# NewThermocouple.net
KiCad netlist of a schematic drawn in Altium Designer
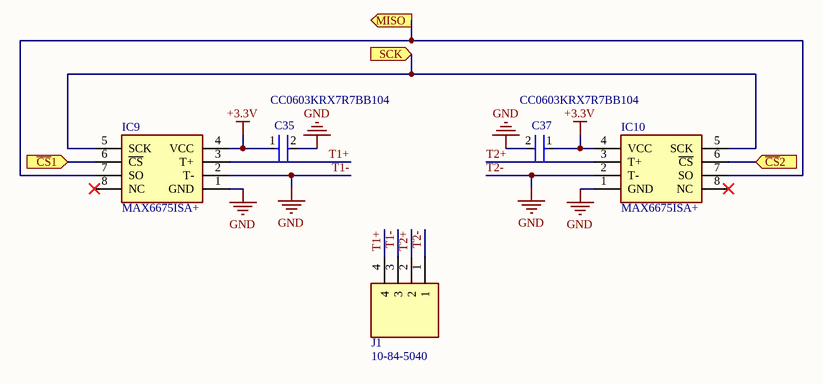
[diagram p0: NewThermocouple.SchDoc]

(export (version "E")
  (design (tool "Eeschema 10.0.6"))
  (components
    (comp (ref "C35")
      (value "CC0603KRX7R7BB104")
      (footprint "FP-CC0603-DA-MFG")
      (description "CAP CER 0.1UF 16V X7R 0603")
      (fields
        (field (name "OCTOPART") "https://octopart.com/cc0603krx7r7bb104-yageo-192941")
        (field (name "TOLERANCE") "0.1")
      )
      (libsource (lib "Altium Content Vault") (part "11868f565c42a9108669ba33697ecf6"))
    )
    (comp (ref "C37")
      (value "CC0603KRX7R7BB104")
      (footprint "FP-CC0603-DA-MFG")
      (description "CAP CER 0.1UF 16V X7R 0603")
      (fields
        (field (name "OCTOPART") "https://octopart.com/cc0603krx7r7bb104-yageo-192941")
        (field (name "TOLERANCE") "0.1")
      )
      (libsource (lib "Altium Content Vault") (part "11868f565c42a9108669ba33697ecf6"))
    )
    (comp (ref "IC9")
      (value "MAX6675ISA+")
      (footprint "SamacSys:SOIC127P600X175-8N")
      (description "Integrated Circuit")
      (fields (field (name "MOUSER2 PART NUMBER") "700-MAX6675ISA"))
      (libsource (lib "") (part "MAX6675ISA+_1"))
    )
    (comp (ref "IC10")
      (value "MAX6675ISA+")
      (footprint "SamacSys:SOIC127P600X175-8N")
      (description "Integrated Circuit")
      (fields (field (name "MOUSER2 PART NUMBER") "700-MAX6675ISA"))
      (libsource (lib "*") (part "MAX6675ISA+"))
    )
    (comp (ref "J1")
      (value "10-84-5040")
      (footprint "SamacSys:10845040")
      (description "Connector")
      (libsource (lib "*") (part "10-84-5040"))
    )
  )
  (nets
    (net (code "1") (name "+3.3V") (class "Default")
      (node (ref "C35") (pin "1") (pinfunction "1_1") (pintype "passive"))
      (node (ref "C37") (pin "1") (pinfunction "1_1") (pintype "passive"))
      (node (ref "IC10") (pin "4") (pinfunction "VCC_4") (pintype "passive"))
      (node (ref "IC9") (pin "4") (pinfunction "VCC_4") (pintype "passive"))
    )
    (net (code "2") (name "/MISO") (class "Default")
      (node (ref "IC10") (pin "7") (pinfunction "SO_7") (pintype "passive"))
      (node (ref "IC9") (pin "7") (pinfunction "SO_7") (pintype "passive"))
    )
    (net (code "3") (name "/SCK") (class "Default")
      (node (ref "IC10") (pin "5") (pinfunction "SCK_5") (pintype "passive"))
      (node (ref "IC9") (pin "5") (pinfunction "SCK_5") (pintype "passive"))
    )
    (net (code "4") (name "/T1+") (class "Default")
      (node (ref "IC9") (pin "3") (pinfunction "T+_3") (pintype "passive"))
      (node (ref "J1") (pin "4") (pinfunction "4_4") (pintype "passive"))
    )
    (net (code "5") (name "/T2+") (class "Default")
      (node (ref "IC10") (pin "3") (pinfunction "T+_3") (pintype "passive"))
      (node (ref "J1") (pin "2") (pinfunction "2_2") (pintype "passive"))
    )
    (net (code "6") (name "/~{CS}1") (class "Default")
      (node (ref "IC9") (pin "6") (pinfunction "~{CS}_6") (pintype "passive"))
    )
    (net (code "7") (name "/~{CS}2") (class "Default")
      (node (ref "IC10") (pin "6") (pinfunction "~{CS}_6") (pintype "passive"))
    )
    (net (code "8") (name "GND") (class "Default")
      (node (ref "C35") (pin "2") (pinfunction "2_2") (pintype "passive"))
      (node (ref "C37") (pin "2") (pinfunction "2_2") (pintype "passive"))
      (node (ref "IC10") (pin "1") (pinfunction "GND_1") (pintype "passive"))
      (node (ref "IC10") (pin "2") (pinfunction "T-_2") (pintype "passive"))
      (node (ref "IC9") (pin "1") (pinfunction "GND_1") (pintype "passive"))
      (node (ref "IC9") (pin "2") (pinfunction "T-_2") (pintype "passive"))
      (node (ref "J1") (pin "1") (pinfunction "1_1") (pintype "passive"))
      (node (ref "J1") (pin "3") (pinfunction "3_3") (pintype "passive"))
    )
    (net (code "9") (name "unconnected-(IC9-NC-Pad8)") (class "Default")
      (node (ref "IC9") (pin "8") (pinfunction "NC_8") (pintype "passive+no_connect"))
    )
    (net (code "10") (name "unconnected-(IC10-NC-Pad8)") (class "Default")
      (node (ref "IC10") (pin "8") (pinfunction "NC_8") (pintype "passive+no_connect"))
    )
  )
)
